# pcb.net
KiCad netlist of a schematic drawn in EAGLE
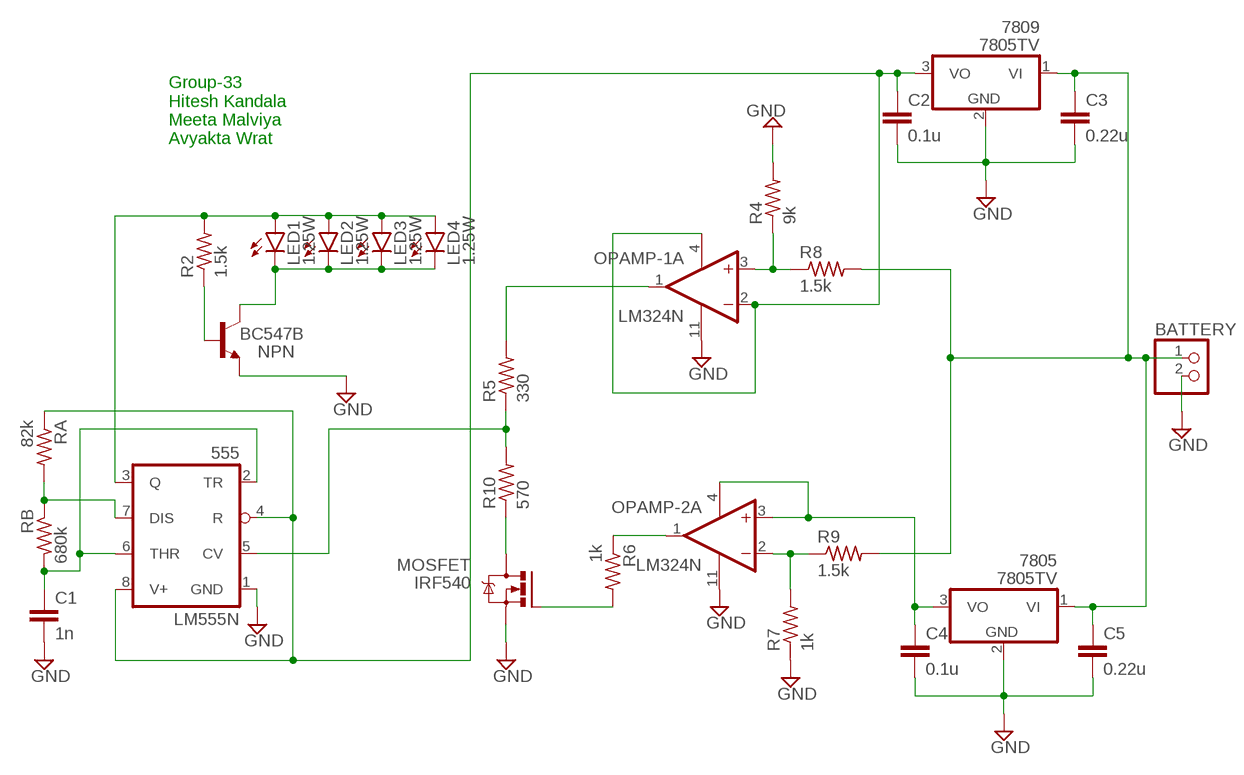
[diagram p0: schematic, sheet 1]

(export (version "E")
  (design (tool "Eeschema 10.0.6"))
  (components
    (comp (ref "555")
      (value "LM555N")
      (footprint "eagle-import:DIL08")
      (libsource (lib "eagle-import") (part "555NLM"))
    )
    (comp (ref "7805")
      (value "7805TV")
      (footprint "eagle-import:TO220V")
      (libsource (lib "eagle-import") (part "78TV05"))
    )
    (comp (ref "7809")
      (value "7805TV")
      (footprint "eagle-import:TO220V")
      (libsource (lib "eagle-import") (part "78TV05"))
    )
    (comp (ref "BATTERY")
      (value "PINHD-1X2")
      (footprint "eagle-import:1X02")
      (libsource (lib "eagle-import") (part "PINHD-1X2"))
    )
    (comp (ref "C1")
      (value "1n")
      (footprint "eagle-import:C050-025X075")
      (libsource (lib "eagle-import") (part "C-EU050-025X075"))
    )
    (comp (ref "C2")
      (value "0.1u")
      (footprint "eagle-import:C050-025X075")
      (libsource (lib "eagle-import") (part "C-EU050-025X075"))
    )
    (comp (ref "C3")
      (value "0.22u")
      (footprint "eagle-import:C050-025X075")
      (libsource (lib "eagle-import") (part "C-EU050-025X075"))
    )
    (comp (ref "C4")
      (value "0.1u")
      (footprint "eagle-import:C050-025X075")
      (libsource (lib "eagle-import") (part "C-EU050-025X075"))
    )
    (comp (ref "C5")
      (value "0.22u")
      (footprint "eagle-import:C050-025X075")
      (libsource (lib "eagle-import") (part "C-EU050-025X075"))
    )
    (comp (ref "LED1")
      (value "1.25W")
      (footprint "eagle-import:LED5MM")
      (libsource (lib "eagle-import") (part "LED5MM"))
    )
    (comp (ref "LED2")
      (value "1.25W")
      (footprint "eagle-import:LED5MM")
      (libsource (lib "eagle-import") (part "LED5MM"))
    )
    (comp (ref "LED3")
      (value "1.25W")
      (footprint "eagle-import:LED5MM")
      (libsource (lib "eagle-import") (part "LED5MM"))
    )
    (comp (ref "LED4")
      (value "1.25W")
      (footprint "eagle-import:LED5MM")
      (libsource (lib "eagle-import") (part "LED5MM"))
    )
    (comp (ref "MOSFET")
      (value "IRF540")
      (footprint "eagle-import:TO220BV")
      (libsource (lib "eagle-import") (part "IRF540"))
    )
    (comp (ref "NPN")
      (value "BC547B")
      (footprint "eagle-import:TO92")
      (libsource (lib "eagle-import") (part "BC547B"))
    )
    (comp (ref "OPAMP-1")
      (value "LM324N")
      (footprint "eagle-import:DIL14")
      (libsource (lib "eagle-import") (part "LM324N"))
    )
    (comp (ref "OPAMP-2")
      (value "LM324N")
      (footprint "eagle-import:DIL14")
      (libsource (lib "eagle-import") (part "LM324N"))
    )
    (comp (ref "R2")
      (value "1.5k")
      (footprint "eagle-import:0207_10")
      (libsource (lib "eagle-import") (part "R-US_0207/10"))
    )
    (comp (ref "R4")
      (value "9k")
      (footprint "eagle-import:0207_10")
      (libsource (lib "eagle-import") (part "R-US_0207/10"))
    )
    (comp (ref "R5")
      (value "330")
      (footprint "eagle-import:0207_10")
      (libsource (lib "eagle-import") (part "R-US_0207/10"))
    )
    (comp (ref "R6")
      (value "1k")
      (footprint "eagle-import:0207_10")
      (libsource (lib "eagle-import") (part "R-US_0207/10"))
    )
    (comp (ref "R7")
      (value "1k")
      (footprint "eagle-import:0207_10")
      (libsource (lib "eagle-import") (part "R-US_0207/10"))
    )
    (comp (ref "R8")
      (value "1.5k")
      (footprint "eagle-import:0207_10")
      (libsource (lib "eagle-import") (part "R-US_0207/10"))
    )
    (comp (ref "R9")
      (value "1.5k")
      (footprint "eagle-import:0207_10")
      (libsource (lib "eagle-import") (part "R-US_0207/10"))
    )
    (comp (ref "R10")
      (value "570")
      (footprint "eagle-import:0207_10")
      (libsource (lib "eagle-import") (part "R-US_0207/10"))
    )
    (comp (ref "RA")
      (value "82k")
      (footprint "eagle-import:0207_10")
      (libsource (lib "eagle-import") (part "R-US_0207/10"))
    )
    (comp (ref "RB")
      (value "680k")
      (footprint "eagle-import:0207_10")
      (libsource (lib "eagle-import") (part "R-US_0207/10"))
    )
  )
  (nets
    (net (code "1") (name "GND") (class "Default")
      (node (ref "555") (pin "1") (pinfunction "GND_1") (pintype "power_in"))
      (node (ref "7805") (pin "2") (pinfunction "GND_2") (pintype "passive"))
      (node (ref "7809") (pin "2") (pinfunction "GND_2") (pintype "passive"))
      (node (ref "BATTERY") (pin "2") (pinfunction "2_2") (pintype "passive"))
      (node (ref "C1") (pin "2") (pinfunction "2_2") (pintype "passive"))
      (node (ref "C2") (pin "2") (pinfunction "2_2") (pintype "passive"))
      (node (ref "C3") (pin "2") (pinfunction "2_2") (pintype "passive"))
      (node (ref "C4") (pin "2") (pinfunction "2_2") (pintype "passive"))
      (node (ref "C5") (pin "2") (pinfunction "2_2") (pintype "passive"))
      (node (ref "MOSFET") (pin "S") (pinfunction "S_S") (pintype "passive"))
      (node (ref "NPN") (pin "1") (pinfunction "E_1") (pintype "passive"))
      (node (ref "OPAMP-1") (pin "11") (pinfunction "V-_11") (pintype "power_in"))
      (node (ref "OPAMP-2") (pin "11") (pinfunction "V-_11") (pintype "power_in"))
      (node (ref "R4") (pin "2") (pinfunction "2_2") (pintype "passive"))
      (node (ref "R7") (pin "1") (pinfunction "1_1") (pintype "passive"))
    )
    (net (code "2") (name "Net-(555-CV)") (class "Default")
      (node (ref "555") (pin "5") (pinfunction "CV_5") (pintype "input"))
      (node (ref "R10") (pin "2") (pinfunction "2_2") (pintype "passive"))
      (node (ref "R5") (pin "1") (pinfunction "1_1") (pintype "passive"))
    )
    (net (code "3") (name "Net-(555-DIS)") (class "Default")
      (node (ref "555") (pin "7") (pinfunction "DIS_7") (pintype "input"))
      (node (ref "RA") (pin "2") (pinfunction "2_2") (pintype "passive"))
      (node (ref "RB") (pin "1") (pinfunction "1_1") (pintype "passive"))
    )
    (net (code "4") (name "Net-(555-Q)") (class "Default")
      (node (ref "555") (pin "3") (pinfunction "Q_3") (pintype "output"))
      (node (ref "LED1") (pin "A") (pinfunction "A_A") (pintype "passive"))
      (node (ref "LED2") (pin "A") (pinfunction "A_A") (pintype "passive"))
      (node (ref "LED3") (pin "A") (pinfunction "A_A") (pintype "passive"))
      (node (ref "LED4") (pin "A") (pinfunction "A_A") (pintype "passive"))
      (node (ref "R2") (pin "2") (pinfunction "2_2") (pintype "passive"))
    )
    (net (code "5") (name "Net-(555-R)") (class "Default")
      (node (ref "555") (pin "4") (pinfunction "R_4") (pintype "input"))
      (node (ref "555") (pin "8") (pinfunction "V+_8") (pintype "power_in"))
      (node (ref "7809") (pin "3") (pinfunction "VO_3") (pintype "passive"))
      (node (ref "C2") (pin "1") (pinfunction "1_1") (pintype "passive"))
      (node (ref "OPAMP-1") (pin "2") (pinfunction "-IN_2") (pintype "input"))
      (node (ref "OPAMP-1") (pin "4") (pinfunction "V+_4") (pintype "power_in"))
      (node (ref "RA") (pin "1") (pinfunction "1_1") (pintype "passive"))
    )
    (net (code "6") (name "Net-(555-THR)") (class "Default")
      (node (ref "555") (pin "2") (pinfunction "TR_2") (pintype "input"))
      (node (ref "555") (pin "6") (pinfunction "THR_6") (pintype "input"))
      (node (ref "C1") (pin "1") (pinfunction "1_1") (pintype "passive"))
      (node (ref "RB") (pin "2") (pinfunction "2_2") (pintype "passive"))
    )
    (net (code "7") (name "Net-(7805-VI)") (class "Default")
      (node (ref "7805") (pin "1") (pinfunction "VI_1") (pintype "input"))
      (node (ref "7809") (pin "1") (pinfunction "VI_1") (pintype "input"))
      (node (ref "BATTERY") (pin "1") (pinfunction "1_1") (pintype "passive"))
      (node (ref "C3") (pin "1") (pinfunction "1_1") (pintype "passive"))
      (node (ref "C5") (pin "1") (pinfunction "1_1") (pintype "passive"))
      (node (ref "R8") (pin "2") (pinfunction "2_2") (pintype "passive"))
      (node (ref "R9") (pin "2") (pinfunction "2_2") (pintype "passive"))
    )
    (net (code "8") (name "Net-(7805-VO)") (class "Default")
      (node (ref "7805") (pin "3") (pinfunction "VO_3") (pintype "passive"))
      (node (ref "C4") (pin "1") (pinfunction "1_1") (pintype "passive"))
      (node (ref "OPAMP-2") (pin "3") (pinfunction "+IN_3") (pintype "input"))
      (node (ref "OPAMP-2") (pin "4") (pinfunction "V+_4") (pintype "power_in"))
    )
    (net (code "9") (name "Net-(LED1-C)") (class "Default")
      (node (ref "LED1") (pin "K") (pinfunction "C_K") (pintype "passive"))
      (node (ref "LED2") (pin "K") (pinfunction "C_K") (pintype "passive"))
      (node (ref "LED3") (pin "K") (pinfunction "C_K") (pintype "passive"))
      (node (ref "LED4") (pin "K") (pinfunction "C_K") (pintype "passive"))
      (node (ref "NPN") (pin "3") (pinfunction "C_3") (pintype "passive"))
    )
    (net (code "10") (name "Net-(MOSFET-PadD)") (class "Default")
      (node (ref "MOSFET") (pin "D") (pinfunction "D_D") (pintype "passive"))
      (node (ref "R10") (pin "1") (pinfunction "1_1") (pintype "passive"))
    )
    (net (code "11") (name "Net-(MOSFET-PadG)") (class "Default")
      (node (ref "MOSFET") (pin "G") (pinfunction "G_G") (pintype "passive"))
      (node (ref "R6") (pin "2") (pinfunction "2_2") (pintype "passive"))
    )
    (net (code "12") (name "Net-(NPN-B)") (class "Default")
      (node (ref "NPN") (pin "2") (pinfunction "B_2") (pintype "passive"))
      (node (ref "R2") (pin "1") (pinfunction "1_1") (pintype "passive"))
    )
    (net (code "13") (name "Net-(OPAMP-1A-+IN)") (class "Default")
      (node (ref "OPAMP-1") (pin "3") (pinfunction "+IN_3") (pintype "input"))
      (node (ref "R4") (pin "1") (pinfunction "1_1") (pintype "passive"))
      (node (ref "R8") (pin "1") (pinfunction "1_1") (pintype "passive"))
    )
    (net (code "14") (name "Net-(OPAMP-1A-OUT)") (class "Default")
      (node (ref "OPAMP-1") (pin "1") (pinfunction "OUT_1") (pintype "output"))
      (node (ref "R5") (pin "2") (pinfunction "2_2") (pintype "passive"))
    )
    (net (code "15") (name "Net-(OPAMP-2A--IN)") (class "Default")
      (node (ref "OPAMP-2") (pin "2") (pinfunction "-IN_2") (pintype "input"))
      (node (ref "R7") (pin "2") (pinfunction "2_2") (pintype "passive"))
      (node (ref "R9") (pin "1") (pinfunction "1_1") (pintype "passive"))
    )
    (net (code "16") (name "Net-(OPAMP-2A-OUT)") (class "Default")
      (node (ref "OPAMP-2") (pin "1") (pinfunction "OUT_1") (pintype "output"))
      (node (ref "R6") (pin "1") (pinfunction "1_1") (pintype "passive"))
    )
  )
)
